# PIC_Schematic.net
KiCad netlist of a schematic drawn in EAGLE
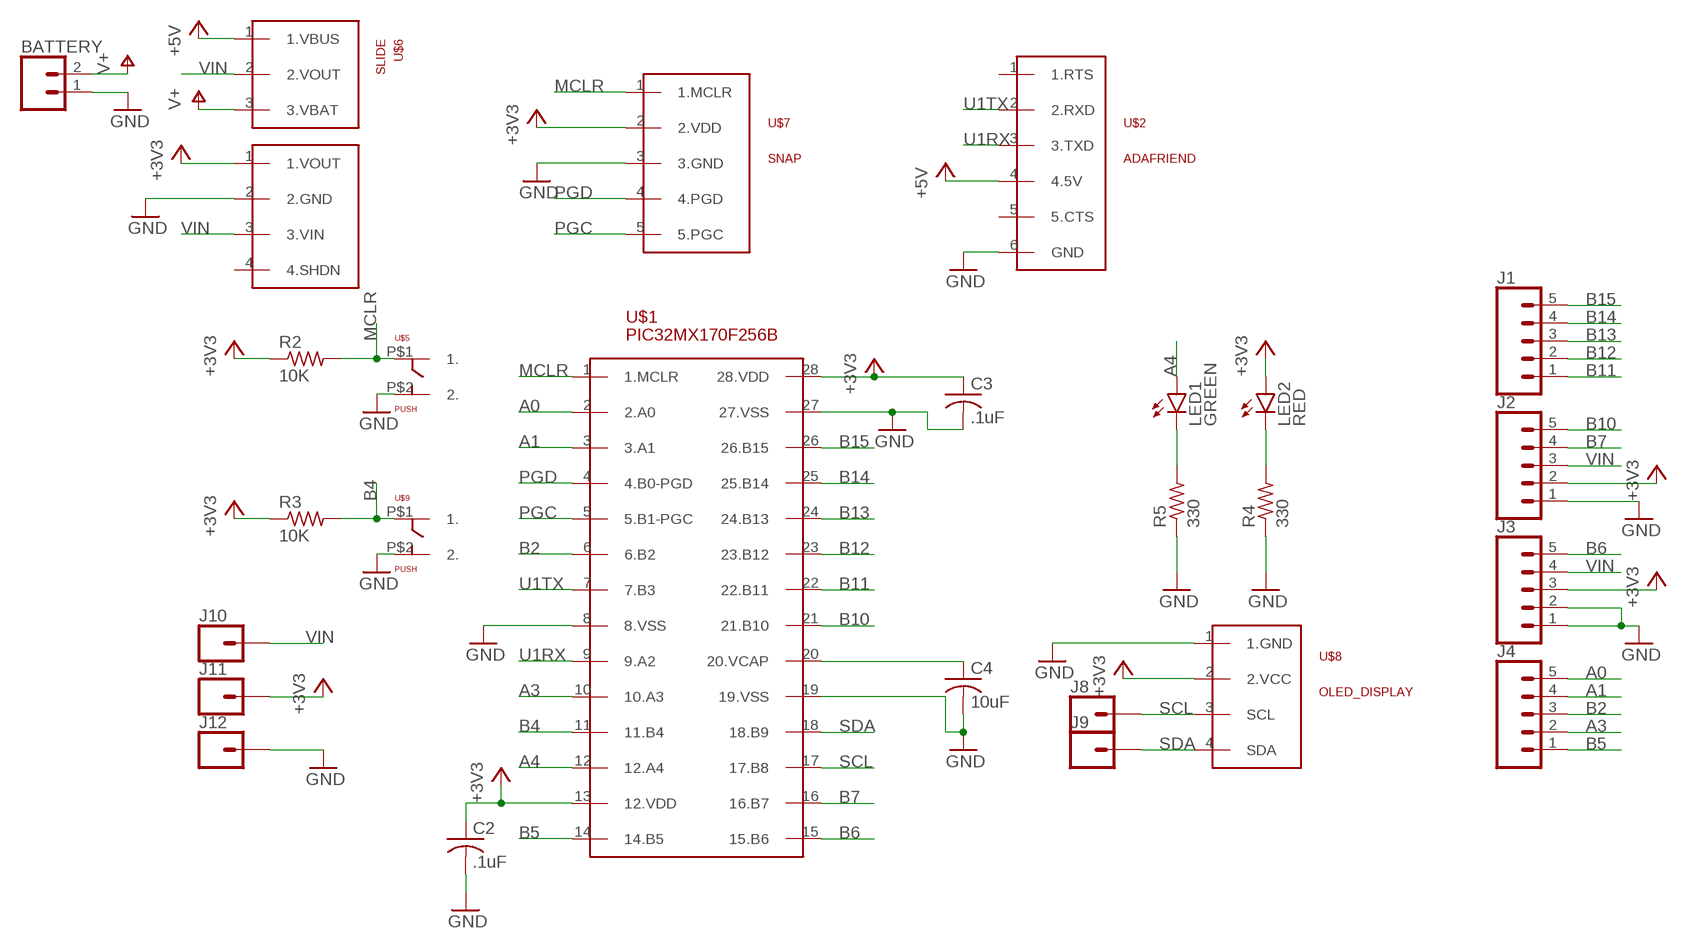
[diagram p0: schematic, sheet 1]

(export (version "E")
  (design (tool "Eeschema 10.0.6"))
  (components
    (comp (ref "BATTERY")
      (value "CONN_02")
      (footprint "eagle-import:1X02")
      (libsource (lib "eagle-import") (part "CONN_02"))
    )
    (comp (ref "C2")
      (value ".1uF")
      (footprint "eagle-import:C025-030X050")
      (libsource (lib "eagle-import") (part "C-US025-030X050"))
    )
    (comp (ref "C3")
      (value ".1uF")
      (footprint "eagle-import:C025-030X050")
      (libsource (lib "eagle-import") (part "C-US025-030X050"))
    )
    (comp (ref "C4")
      (value "10uF")
      (footprint "eagle-import:C025-030X050")
      (libsource (lib "eagle-import") (part "C-US025-030X050"))
    )
    (comp (ref "J1")
      (value "CONN_05")
      (footprint "eagle-import:1X05")
      (libsource (lib "eagle-import") (part "CONN_05"))
    )
    (comp (ref "J2")
      (value "CONN_05")
      (footprint "eagle-import:1X05")
      (libsource (lib "eagle-import") (part "CONN_05"))
    )
    (comp (ref "J3")
      (value "CONN_05")
      (footprint "eagle-import:1X05")
      (libsource (lib "eagle-import") (part "CONN_05"))
    )
    (comp (ref "J4")
      (value "CONN_05")
      (footprint "eagle-import:1X05")
      (libsource (lib "eagle-import") (part "CONN_05"))
    )
    (comp (ref "J8")
      (value "CONN_01")
      (footprint "eagle-import:1X01")
      (libsource (lib "eagle-import") (part "CONN_01"))
    )
    (comp (ref "J9")
      (value "CONN_01")
      (footprint "eagle-import:1X01")
      (libsource (lib "eagle-import") (part "CONN_01"))
    )
    (comp (ref "J10")
      (value "CONN_01")
      (footprint "eagle-import:1X01")
      (libsource (lib "eagle-import") (part "CONN_01"))
    )
    (comp (ref "J11")
      (value "CONN_01")
      (footprint "eagle-import:1X01")
      (libsource (lib "eagle-import") (part "CONN_01"))
    )
    (comp (ref "J12")
      (value "CONN_01")
      (footprint "eagle-import:1X01")
      (libsource (lib "eagle-import") (part "CONN_01"))
    )
    (comp (ref "LED1")
      (value "GREEN")
      (footprint "eagle-import:LED3MM")
      (libsource (lib "eagle-import") (part "LED3MM"))
    )
    (comp (ref "LED2")
      (value "RED")
      (footprint "eagle-import:LED3MM")
      (libsource (lib "eagle-import") (part "LED3MM"))
    )
    (comp (ref "R2")
      (value "10K")
      (footprint "eagle-import:0207_10")
      (libsource (lib "eagle-import") (part "R-US_0207/10"))
    )
    (comp (ref "R3")
      (value "10K")
      (footprint "eagle-import:0207_10")
      (libsource (lib "eagle-import") (part "R-US_0207/10"))
    )
    (comp (ref "R4")
      (value "330")
      (footprint "eagle-import:0207_10")
      (libsource (lib "eagle-import") (part "R-US_0207/10"))
    )
    (comp (ref "R5")
      (value "330")
      (footprint "eagle-import:0207_10")
      (libsource (lib "eagle-import") (part "R-US_0207/10"))
    )
    (comp (ref "U$1")
      (value "PIC32MX170F256B")
      (footprint "eagle-import:DIL28-3")
      (libsource (lib "eagle-import") (part "PIC32MX170F256B"))
    )
    (comp (ref "U$2")
      (value "ADAFRIEND")
      (footprint "eagle-import:ADAFRIEND")
      (libsource (lib "eagle-import") (part "ADAFRIEND"))
    )
    (comp (ref "U$3")
      (value "POLOLU_3V3")
      (footprint "eagle-import:POLOLU_3V3")
      (libsource (lib "eagle-import") (part "POLOLU_3V3"))
    )
    (comp (ref "U$5")
      (value "PUSH")
      (footprint "eagle-import:PUSH")
      (libsource (lib "eagle-import") (part "PUSH"))
    )
    (comp (ref "U$6")
      (value "SLIDE")
      (footprint "eagle-import:SLIDE")
      (libsource (lib "eagle-import") (part "SLIDE"))
    )
    (comp (ref "U$7")
      (value "SNAP")
      (footprint "eagle-import:SNAP")
      (libsource (lib "eagle-import") (part "SNAP"))
    )
    (comp (ref "U$8")
      (value "OLED_DISPLAY")
      (footprint "eagle-import:OLED_DISPLAY")
      (libsource (lib "eagle-import") (part "OLED_DISPLAY"))
    )
    (comp (ref "U$9")
      (value "PUSH")
      (footprint "eagle-import:PUSH")
      (libsource (lib "eagle-import") (part "PUSH"))
    )
  )
  (nets
    (net (code "1") (name "+3V3") (class "Default")
      (node (ref "C2") (pin "1") (pinfunction "1_1") (pintype "passive"))
      (node (ref "C3") (pin "1") (pinfunction "1_1") (pintype "passive"))
      (node (ref "J11") (pin "1") (pinfunction "1_1") (pintype "passive"))
      (node (ref "J2") (pin "2") (pinfunction "2_2") (pintype "passive"))
      (node (ref "J3") (pin "3") (pinfunction "3_3") (pintype "passive"))
      (node (ref "LED2") (pin "A") (pinfunction "A_A") (pintype "passive"))
      (node (ref "R2") (pin "1") (pinfunction "1_1") (pintype "passive"))
      (node (ref "R3") (pin "1") (pinfunction "1_1") (pintype "passive"))
      (node (ref "U$1") (pin "13") (pinfunction "12.VDD_13") (pintype "bidirectional"))
      (node (ref "U$1") (pin "28") (pinfunction "28.VDD_28") (pintype "bidirectional"))
      (node (ref "U$3") (pin "1") (pinfunction "1.VOUT_1") (pintype "bidirectional"))
      (node (ref "U$7") (pin "2") (pinfunction "2.VDD_2") (pintype "bidirectional"))
      (node (ref "U$8") (pin "2") (pinfunction "2.VCC_2") (pintype "bidirectional"))
    )
    (net (code "2") (name "+5V") (class "Default")
      (node (ref "U$2") (pin "4") (pinfunction "4.5V_4") (pintype "bidirectional"))
      (node (ref "U$6") (pin "1") (pinfunction "1.VBUS_1") (pintype "bidirectional"))
    )
    (net (code "3") (name "/A0") (class "Default")
      (node (ref "J4") (pin "5") (pinfunction "5_5") (pintype "passive"))
      (node (ref "U$1") (pin "2") (pinfunction "2.A0_2") (pintype "bidirectional"))
    )
    (net (code "4") (name "/A1") (class "Default")
      (node (ref "J4") (pin "4") (pinfunction "4_4") (pintype "passive"))
      (node (ref "U$1") (pin "3") (pinfunction "3.A1_3") (pintype "bidirectional"))
    )
    (net (code "5") (name "/A3") (class "Default")
      (node (ref "J4") (pin "2") (pinfunction "2_2") (pintype "passive"))
      (node (ref "U$1") (pin "10") (pinfunction "10.A3_10") (pintype "bidirectional"))
    )
    (net (code "6") (name "/A4") (class "Default")
      (node (ref "LED1") (pin "A") (pinfunction "A_A") (pintype "passive"))
      (node (ref "U$1") (pin "12") (pinfunction "12.A4_12") (pintype "bidirectional"))
    )
    (net (code "7") (name "/B2") (class "Default")
      (node (ref "J4") (pin "3") (pinfunction "3_3") (pintype "passive"))
      (node (ref "U$1") (pin "6") (pinfunction "6.B2_6") (pintype "bidirectional"))
    )
    (net (code "8") (name "/B4") (class "Default")
      (node (ref "R3") (pin "2") (pinfunction "2_2") (pintype "passive"))
      (node (ref "U$1") (pin "11") (pinfunction "11.B4_11") (pintype "bidirectional"))
      (node (ref "U$9") (pin "P$1") (pinfunction "1._P$1") (pintype "bidirectional"))
    )
    (net (code "9") (name "/B5") (class "Default")
      (node (ref "J4") (pin "1") (pinfunction "1_1") (pintype "passive"))
      (node (ref "U$1") (pin "14") (pinfunction "14.B5_14") (pintype "bidirectional"))
    )
    (net (code "10") (name "/B6") (class "Default")
      (node (ref "J3") (pin "5") (pinfunction "5_5") (pintype "passive"))
      (node (ref "U$1") (pin "15") (pinfunction "15.B6_15") (pintype "bidirectional"))
    )
    (net (code "11") (name "/B7") (class "Default")
      (node (ref "J2") (pin "4") (pinfunction "4_4") (pintype "passive"))
      (node (ref "U$1") (pin "16") (pinfunction "16.B7_16") (pintype "bidirectional"))
    )
    (net (code "12") (name "/B10") (class "Default")
      (node (ref "J2") (pin "5") (pinfunction "5_5") (pintype "passive"))
      (node (ref "U$1") (pin "21") (pinfunction "21.B10_21") (pintype "bidirectional"))
    )
    (net (code "13") (name "/B11") (class "Default")
      (node (ref "J1") (pin "1") (pinfunction "1_1") (pintype "passive"))
      (node (ref "U$1") (pin "22") (pinfunction "22.B11_22") (pintype "bidirectional"))
    )
    (net (code "14") (name "/B12") (class "Default")
      (node (ref "J1") (pin "2") (pinfunction "2_2") (pintype "passive"))
      (node (ref "U$1") (pin "23") (pinfunction "23.B12_23") (pintype "bidirectional"))
    )
    (net (code "15") (name "/B13") (class "Default")
      (node (ref "J1") (pin "3") (pinfunction "3_3") (pintype "passive"))
      (node (ref "U$1") (pin "24") (pinfunction "24.B13_24") (pintype "bidirectional"))
    )
    (net (code "16") (name "/B14") (class "Default")
      (node (ref "J1") (pin "4") (pinfunction "4_4") (pintype "passive"))
      (node (ref "U$1") (pin "25") (pinfunction "25.B14_25") (pintype "bidirectional"))
    )
    (net (code "17") (name "/B15") (class "Default")
      (node (ref "J1") (pin "5") (pinfunction "5_5") (pintype "passive"))
      (node (ref "U$1") (pin "26") (pinfunction "26.B15_26") (pintype "bidirectional"))
    )
    (net (code "18") (name "/MCLR") (class "Default")
      (node (ref "R2") (pin "2") (pinfunction "2_2") (pintype "passive"))
      (node (ref "U$1") (pin "1") (pinfunction "1.MCLR_1") (pintype "bidirectional"))
      (node (ref "U$5") (pin "P$1") (pinfunction "1._P$1") (pintype "bidirectional"))
      (node (ref "U$7") (pin "1") (pinfunction "1.MCLR_1") (pintype "bidirectional"))
    )
    (net (code "19") (name "/PGC") (class "Default")
      (node (ref "U$1") (pin "5") (pinfunction "5.B1-PGC_5") (pintype "bidirectional"))
      (node (ref "U$7") (pin "5") (pinfunction "5.PGC_5") (pintype "bidirectional"))
    )
    (net (code "20") (name "/PGD") (class "Default")
      (node (ref "U$1") (pin "4") (pinfunction "4.B0-PGD_4") (pintype "bidirectional"))
      (node (ref "U$7") (pin "4") (pinfunction "4.PGD_4") (pintype "bidirectional"))
    )
    (net (code "21") (name "/SCL") (class "Default")
      (node (ref "J8") (pin "1") (pinfunction "1_1") (pintype "passive"))
      (node (ref "U$1") (pin "17") (pinfunction "17.B8_17") (pintype "bidirectional"))
      (node (ref "U$8") (pin "3") (pinfunction "SCL_3") (pintype "bidirectional"))
    )
    (net (code "22") (name "/SDA") (class "Default")
      (node (ref "J9") (pin "1") (pinfunction "1_1") (pintype "passive"))
      (node (ref "U$1") (pin "18") (pinfunction "18.B9_18") (pintype "bidirectional"))
      (node (ref "U$8") (pin "4") (pinfunction "SDA_4") (pintype "bidirectional"))
    )
    (net (code "23") (name "/U1RX") (class "Default")
      (node (ref "U$1") (pin "9") (pinfunction "9.A2_9") (pintype "bidirectional"))
      (node (ref "U$2") (pin "3") (pinfunction "3.TXD_3") (pintype "bidirectional"))
    )
    (net (code "24") (name "/U1TX") (class "Default")
      (node (ref "U$1") (pin "7") (pinfunction "7.B3_7") (pintype "bidirectional"))
      (node (ref "U$2") (pin "2") (pinfunction "2.RXD_2") (pintype "bidirectional"))
    )
    (net (code "25") (name "/VIN") (class "Default")
      (node (ref "J10") (pin "1") (pinfunction "1_1") (pintype "passive"))
      (node (ref "J2") (pin "3") (pinfunction "3_3") (pintype "passive"))
      (node (ref "J3") (pin "4") (pinfunction "4_4") (pintype "passive"))
      (node (ref "U$3") (pin "3") (pinfunction "3.VIN_3") (pintype "bidirectional"))
      (node (ref "U$6") (pin "2") (pinfunction "2.VOUT_2") (pintype "bidirectional"))
    )
    (net (code "26") (name "GND") (class "Default")
      (node (ref "BATTERY") (pin "1") (pinfunction "1_1") (pintype "passive"))
      (node (ref "C2") (pin "2") (pinfunction "2_2") (pintype "passive"))
      (node (ref "C3") (pin "2") (pinfunction "2_2") (pintype "passive"))
      (node (ref "C4") (pin "2") (pinfunction "2_2") (pintype "passive"))
      (node (ref "J12") (pin "1") (pinfunction "1_1") (pintype "passive"))
      (node (ref "J2") (pin "1") (pinfunction "1_1") (pintype "passive"))
      (node (ref "J3") (pin "1") (pinfunction "1_1") (pintype "passive"))
      (node (ref "J3") (pin "2") (pinfunction "2_2") (pintype "passive"))
      (node (ref "R4") (pin "1") (pinfunction "1_1") (pintype "passive"))
      (node (ref "R5") (pin "1") (pinfunction "1_1") (pintype "passive"))
      (node (ref "U$1") (pin "19") (pinfunction "19.VSS_19") (pintype "bidirectional"))
      (node (ref "U$1") (pin "27") (pinfunction "27.VSS_27") (pintype "bidirectional"))
      (node (ref "U$1") (pin "8") (pinfunction "8.VSS_8") (pintype "bidirectional"))
      (node (ref "U$2") (pin "6") (pinfunction "GND_6") (pintype "bidirectional"))
      (node (ref "U$3") (pin "2") (pinfunction "2.GND_2") (pintype "bidirectional"))
      (node (ref "U$5") (pin "P$2") (pinfunction "2._P$2") (pintype "bidirectional"))
      (node (ref "U$7") (pin "3") (pinfunction "3.GND_3") (pintype "bidirectional"))
      (node (ref "U$8") (pin "1") (pinfunction "1.GND_1") (pintype "bidirectional"))
      (node (ref "U$9") (pin "P$2") (pinfunction "2._P$2") (pintype "bidirectional"))
    )
    (net (code "27") (name "Net-(LED1-C)") (class "Default")
      (node (ref "LED1") (pin "K") (pinfunction "C_K") (pintype "passive"))
      (node (ref "R5") (pin "2") (pinfunction "2_2") (pintype "passive"))
    )
    (net (code "28") (name "Net-(LED2-C)") (class "Default")
      (node (ref "LED2") (pin "K") (pinfunction "C_K") (pintype "passive"))
      (node (ref "R4") (pin "2") (pinfunction "2_2") (pintype "passive"))
    )
    (net (code "29") (name "Net-(U$1-20.VCAP)") (class "Default")
      (node (ref "C4") (pin "1") (pinfunction "1_1") (pintype "passive"))
      (node (ref "U$1") (pin "20") (pinfunction "20.VCAP_20") (pintype "bidirectional"))
    )
    (net (code "30") (name "V+") (class "Default")
      (node (ref "BATTERY") (pin "2") (pinfunction "2_2") (pintype "passive"))
      (node (ref "U$6") (pin "3") (pinfunction "3.VBAT_3") (pintype "bidirectional"))
    )
    (net (code "31") (name "unconnected-(U$2-1.RTS-Pad1)") (class "Default")
      (node (ref "U$2") (pin "1") (pinfunction "1.RTS_1") (pintype "bidirectional"))
    )
    (net (code "32") (name "unconnected-(U$2-5.CTS-Pad5)") (class "Default")
      (node (ref "U$2") (pin "5") (pinfunction "5.CTS_5") (pintype "bidirectional"))
    )
    (net (code "33") (name "unconnected-(U$3-4.SHDN-Pad4)") (class "Default")
      (node (ref "U$3") (pin "4") (pinfunction "4.SHDN_4") (pintype "bidirectional"))
    )
  )
)
